# Arduino-Pro-Mini_195x195inch.net
KiCad netlist of a schematic drawn in EAGLE
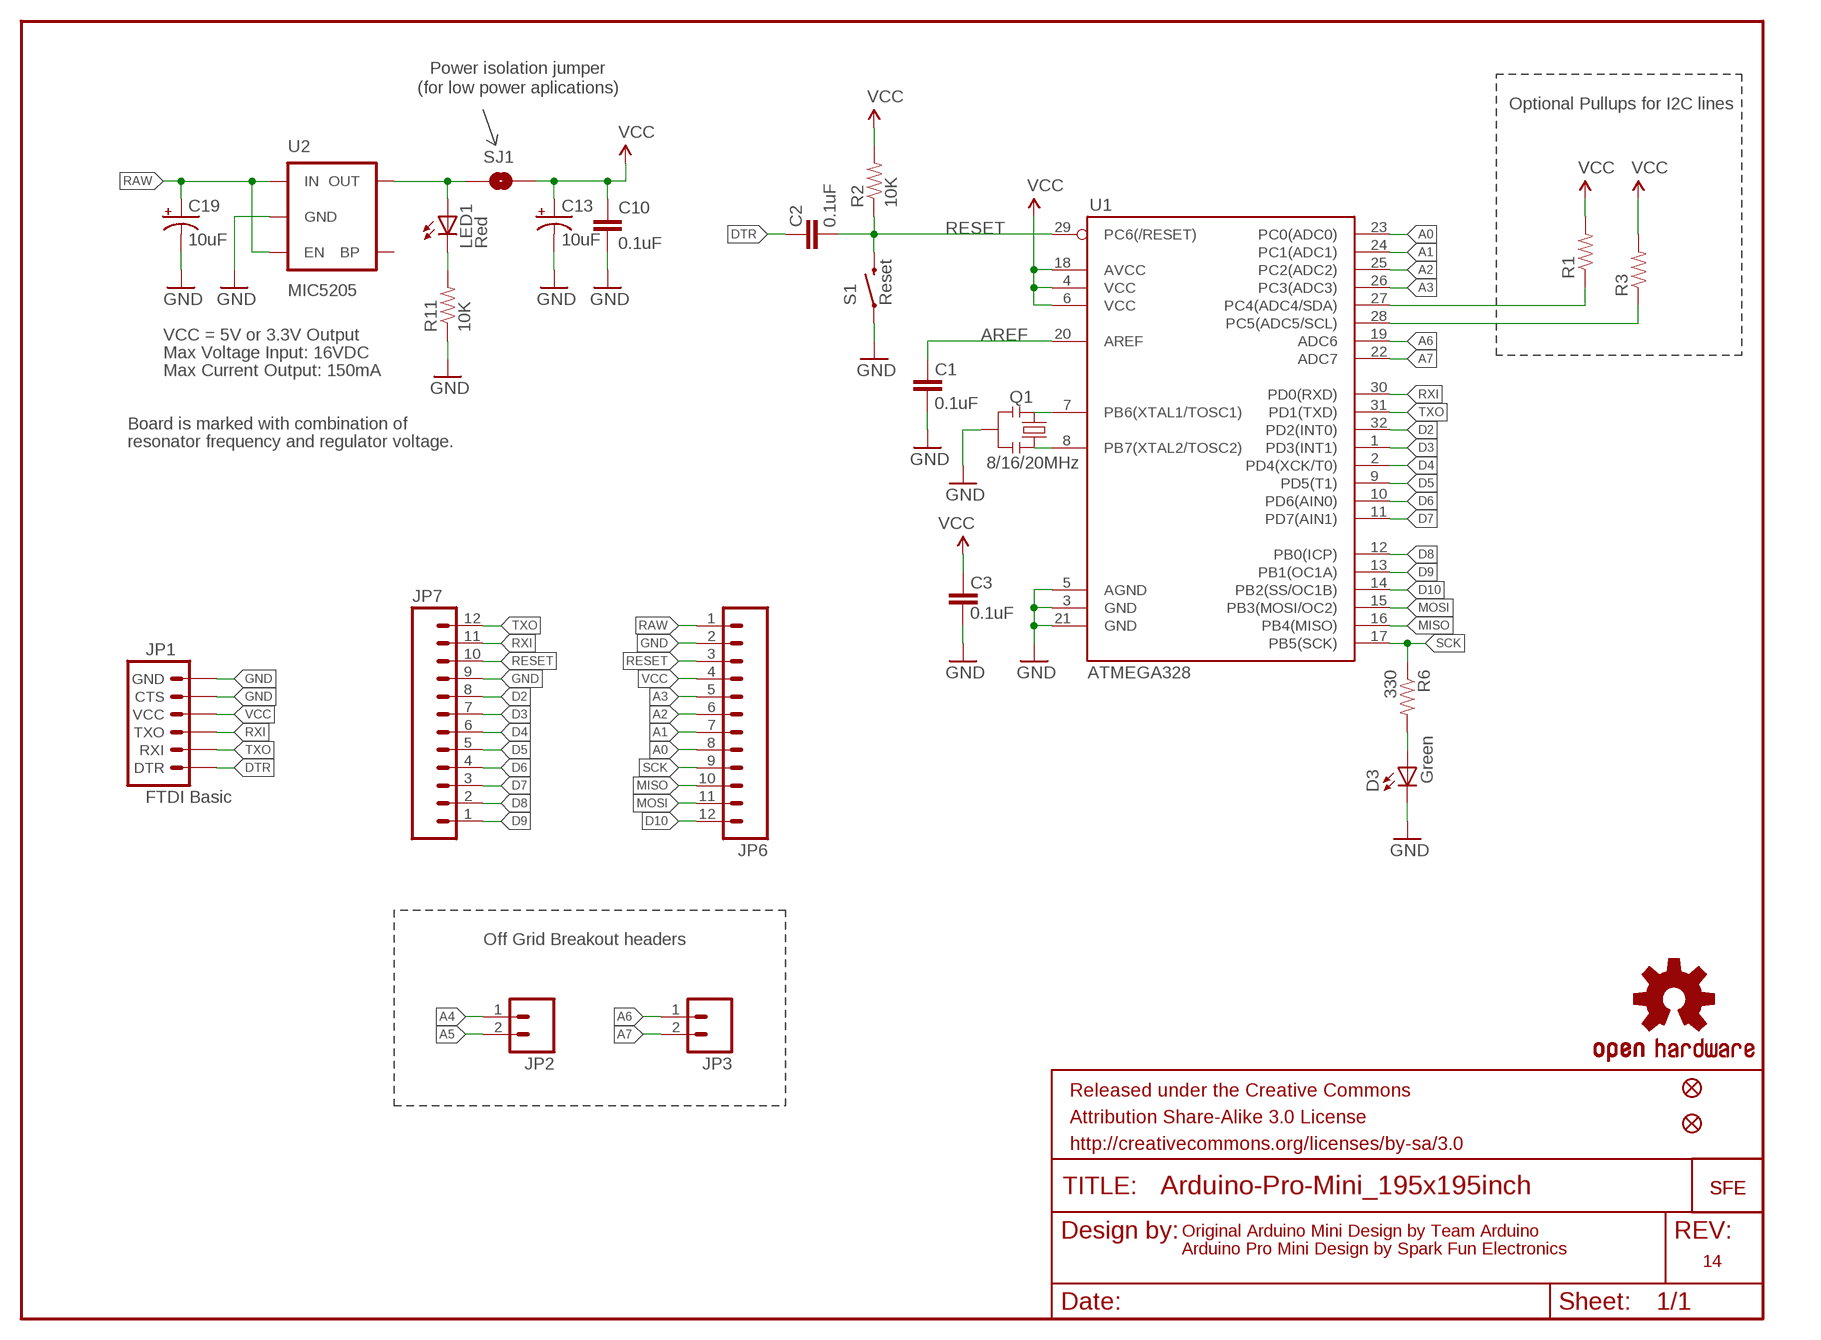
[diagram p0: schematic, sheet 1]

(export (version "E")
  (design (tool "Eeschema 10.0.6"))
  (components
    (comp (ref "C1")
      (value "0.1uF")
      (footprint "eagle-import:0603-CAP")
      (libsource (lib "eagle-import") (part "CAP0603-CAP"))
    )
    (comp (ref "C2")
      (value "0.1uF")
      (footprint "eagle-import:0603-CAP")
      (libsource (lib "eagle-import") (part "CAP0603-CAP"))
    )
    (comp (ref "C3")
      (value "0.1uF")
      (footprint "eagle-import:0603-CAP")
      (libsource (lib "eagle-import") (part "CAP0603-CAP"))
    )
    (comp (ref "C10")
      (value "0.1uF")
      (footprint "eagle-import:0603-CAP")
      (libsource (lib "eagle-import") (part "CAP0603-CAP"))
    )
    (comp (ref "C13")
      (value "10uF")
      (footprint "eagle-import:EIA3216")
      (libsource (lib "eagle-import") (part "CAP_POL1206"))
    )
    (comp (ref "C19")
      (value "10uF")
      (footprint "eagle-import:EIA3216")
      (libsource (lib "eagle-import") (part "CAP_POL1206"))
    )
    (comp (ref "D3")
      (value "Green")
      (footprint "eagle-import:0603-LED-ALT1")
      (libsource (lib "eagle-import") (part "LED"))
    )
    (comp (ref "FRAME1")
      (value "FRAME-LETTER")
      (footprint "eagle-import:CREATIVE_COMMONS")
      (libsource (lib "eagle-import") (part "FRAME-LETTER"))
    )
    (comp (ref "JP1")
      (value "FTDI Basic")
      (footprint "eagle-import:1X06")
      (libsource (lib "eagle-import") (part "ARDUINO_SERIAL_PROGRAMPTH"))
    )
    (comp (ref "JP2")
      (value "M02PTH")
      (footprint "eagle-import:1X02")
      (libsource (lib "eagle-import") (part "M02PTH"))
    )
    (comp (ref "JP3")
      (value "M02PTH")
      (footprint "eagle-import:1X02")
      (libsource (lib "eagle-import") (part "M02PTH"))
    )
    (comp (ref "JP5")
      (value "FIDUCIALUFIDUCIAL")
      (footprint "eagle-import:MICRO-FIDUCIAL")
      (libsource (lib "eagle-import") (part "FIDUCIALUFIDUCIAL"))
    )
    (comp (ref "JP6")
      (value "M12PTH")
      (footprint "eagle-import:1X12")
      (libsource (lib "eagle-import") (part "M12PTH"))
    )
    (comp (ref "JP7")
      (value "M12PTH")
      (footprint "eagle-import:1X12")
      (libsource (lib "eagle-import") (part "M12PTH"))
    )
    (comp (ref "JP8")
      (value "FIDUCIALUFIDUCIAL")
      (footprint "eagle-import:MICRO-FIDUCIAL")
      (libsource (lib "eagle-import") (part "FIDUCIALUFIDUCIAL"))
    )
    (comp (ref "LED1")
      (value "Red")
      (footprint "eagle-import:0603-LED-ALT1")
      (libsource (lib "eagle-import") (part "LED"))
    )
    (comp (ref "Q1")
      (value "8/16/20MHz")
      (footprint "eagle-import:RESONATOR-SMD-1_1")
      (libsource (lib "eagle-import") (part "RESONATOR1{colon}1"))
    )
    (comp (ref "R1")
      (value "RESISTOR0603-RES")
      (footprint "eagle-import:0603-RES")
      (libsource (lib "eagle-import") (part "RESISTOR0603-RES"))
    )
    (comp (ref "R2")
      (value "10K")
      (footprint "eagle-import:0603-RES")
      (libsource (lib "eagle-import") (part "RESISTOR0603-RES"))
    )
    (comp (ref "R3")
      (value "RESISTOR0603-RES")
      (footprint "eagle-import:0603-RES")
      (libsource (lib "eagle-import") (part "RESISTOR0603-RES"))
    )
    (comp (ref "R6")
      (value "330")
      (footprint "eagle-import:0603-RES")
      (libsource (lib "eagle-import") (part "RESISTOR0603-RES"))
    )
    (comp (ref "R11")
      (value "10K")
      (footprint "eagle-import:0603-RES")
      (libsource (lib "eagle-import") (part "RESISTOR0603-RES"))
    )
    (comp (ref "S1")
      (value "Reset")
      (footprint "eagle-import:TACTILE-SWITCH-SMD-ALT01")
      (libsource (lib "eagle-import") (part "SWITCH-MOMENTARY-2SMD-ALT01"))
    )
    (comp (ref "SJ1")
      (value "SOLDERJUMPERNC")
      (footprint "eagle-import:SJ_2S")
      (libsource (lib "eagle-import") (part "SOLDERJUMPERNC"))
    )
    (comp (ref "U$1")
      (value "LOGO-SFESK")
      (footprint "eagle-import:SFE-LOGO-FLAME")
      (libsource (lib "eagle-import") (part "LOGO-SFESK"))
    )
    (comp (ref "U$3")
      (value "OSHW-LOGOS")
      (footprint "eagle-import:OSHW-LOGO-S")
      (libsource (lib "eagle-import") (part "OSHW-LOGOS"))
    )
    (comp (ref "U$11")
      (value "LOGO-SFENEW")
      (footprint "eagle-import:SFE-NEW-WEBLOGO")
      (libsource (lib "eagle-import") (part "LOGO-SFENEW"))
    )
    (comp (ref "U1")
      (value "ATMEGA328")
      (footprint "eagle-import:TQFP32-08")
      (libsource (lib "eagle-import") (part "ATMEGA168"))
    )
    (comp (ref "U2")
      (value "MIC5205")
      (footprint "eagle-import:SOT23-5")
      (libsource (lib "eagle-import") (part "V_REG_LDOSMD"))
    )
  )
  (nets
    (net (code "1") (name "/AREF") (class "Default")
      (node (ref "C1") (pin "2") (pinfunction "2_2") (pintype "passive"))
      (node (ref "U1") (pin "20") (pinfunction "AREF_20") (pintype "bidirectional"))
    )
    (net (code "2") (name "A0") (class "Default")
      (node (ref "JP6") (pin "8") (pinfunction "8_8") (pintype "passive"))
      (node (ref "U1") (pin "23") (pinfunction "PC0(ADC0)_23") (pintype "bidirectional"))
    )
    (net (code "3") (name "A1") (class "Default")
      (node (ref "JP6") (pin "7") (pinfunction "7_7") (pintype "passive"))
      (node (ref "U1") (pin "24") (pinfunction "PC1(ADC1)_24") (pintype "bidirectional"))
    )
    (net (code "4") (name "A2") (class "Default")
      (node (ref "JP6") (pin "6") (pinfunction "6_6") (pintype "passive"))
      (node (ref "U1") (pin "25") (pinfunction "PC2(ADC2)_25") (pintype "bidirectional"))
    )
    (net (code "5") (name "A3") (class "Default")
      (node (ref "JP6") (pin "5") (pinfunction "5_5") (pintype "passive"))
      (node (ref "U1") (pin "26") (pinfunction "PC3(ADC3)_26") (pintype "bidirectional"))
    )
    (net (code "6") (name "A4") (class "Default")
      (node (ref "JP2") (pin "1") (pinfunction "1_1") (pintype "passive"))
      (node (ref "R1") (pin "1") (pinfunction "1_1") (pintype "passive"))
      (node (ref "U1") (pin "27") (pinfunction "PC4(ADC4/SDA)_27") (pintype "bidirectional"))
    )
    (net (code "7") (name "A5") (class "Default")
      (node (ref "JP2") (pin "2") (pinfunction "2_2") (pintype "passive"))
      (node (ref "R3") (pin "1") (pinfunction "1_1") (pintype "passive"))
      (node (ref "U1") (pin "28") (pinfunction "PC5(ADC5/SCL)_28") (pintype "bidirectional"))
    )
    (net (code "8") (name "A6") (class "Default")
      (node (ref "JP3") (pin "1") (pinfunction "1_1") (pintype "passive"))
      (node (ref "U1") (pin "19") (pinfunction "ADC6_19") (pintype "bidirectional"))
    )
    (net (code "9") (name "A7") (class "Default")
      (node (ref "JP3") (pin "2") (pinfunction "2_2") (pintype "passive"))
      (node (ref "U1") (pin "22") (pinfunction "ADC7_22") (pintype "bidirectional"))
    )
    (net (code "10") (name "D2") (class "Default")
      (node (ref "JP7") (pin "8") (pinfunction "8_8") (pintype "passive"))
      (node (ref "U1") (pin "32") (pinfunction "PD2(INT0)_32") (pintype "bidirectional"))
    )
    (net (code "11") (name "D3") (class "Default")
      (node (ref "JP7") (pin "7") (pinfunction "7_7") (pintype "passive"))
      (node (ref "U1") (pin "1") (pinfunction "PD3(INT1)_1") (pintype "bidirectional"))
    )
    (net (code "12") (name "D4") (class "Default")
      (node (ref "JP7") (pin "6") (pinfunction "6_6") (pintype "passive"))
      (node (ref "U1") (pin "2") (pinfunction "PD4(XCK/T0)_2") (pintype "bidirectional"))
    )
    (net (code "13") (name "D5") (class "Default")
      (node (ref "JP7") (pin "5") (pinfunction "5_5") (pintype "passive"))
      (node (ref "U1") (pin "9") (pinfunction "PD5(T1)_9") (pintype "bidirectional"))
    )
    (net (code "14") (name "D6") (class "Default")
      (node (ref "JP7") (pin "4") (pinfunction "4_4") (pintype "passive"))
      (node (ref "U1") (pin "10") (pinfunction "PD6(AIN0)_10") (pintype "bidirectional"))
    )
    (net (code "15") (name "D7") (class "Default")
      (node (ref "JP7") (pin "3") (pinfunction "3_3") (pintype "passive"))
      (node (ref "U1") (pin "11") (pinfunction "PD7(AIN1)_11") (pintype "bidirectional"))
    )
    (net (code "16") (name "D8") (class "Default")
      (node (ref "JP7") (pin "2") (pinfunction "2_2") (pintype "passive"))
      (node (ref "U1") (pin "12") (pinfunction "PB0(ICP)_12") (pintype "bidirectional"))
    )
    (net (code "17") (name "D9") (class "Default")
      (node (ref "JP7") (pin "1") (pinfunction "1_1") (pintype "passive"))
      (node (ref "U1") (pin "13") (pinfunction "PB1(OC1A)_13") (pintype "bidirectional"))
    )
    (net (code "18") (name "D10") (class "Default")
      (node (ref "JP6") (pin "12") (pinfunction "12_12") (pintype "passive"))
      (node (ref "U1") (pin "14") (pinfunction "PB2(SS/OC1B)_14") (pintype "bidirectional"))
    )
    (net (code "19") (name "DTR") (class "Default")
      (node (ref "C2") (pin "2") (pinfunction "2_2") (pintype "passive"))
      (node (ref "JP1") (pin "1") (pinfunction "DTR_1") (pintype "passive"))
    )
    (net (code "20") (name "GND") (class "Default")
      (node (ref "C1") (pin "1") (pinfunction "1_1") (pintype "passive"))
      (node (ref "C10") (pin "2") (pinfunction "2_2") (pintype "passive"))
      (node (ref "C13") (pin "C") (pinfunction "-_C") (pintype "passive"))
      (node (ref "C19") (pin "C") (pinfunction "-_C") (pintype "passive"))
      (node (ref "C3") (pin "1") (pinfunction "1_1") (pintype "passive"))
      (node (ref "D3") (pin "C") (pinfunction "C_C") (pintype "passive"))
      (node (ref "JP1") (pin "5") (pinfunction "CTS_5") (pintype "passive"))
      (node (ref "JP1") (pin "6") (pinfunction "GND_6") (pintype "passive"))
      (node (ref "JP6") (pin "2") (pinfunction "2_2") (pintype "passive"))
      (node (ref "JP7") (pin "9") (pinfunction "9_9") (pintype "passive"))
      (node (ref "Q1") (pin "2") (pinfunction "2_2") (pintype "passive"))
      (node (ref "R11") (pin "1") (pinfunction "1_1") (pintype "passive"))
      (node (ref "S1") (pin "1") (pinfunction "1_1") (pintype "passive"))
      (node (ref "S1") (pin "2") (pinfunction "1_2") (pintype "passive"))
      (node (ref "U1") (pin "21") (pinfunction "GND_21") (pintype "bidirectional"))
      (node (ref "U1") (pin "3") (pinfunction "GND_3") (pintype "bidirectional"))
      (node (ref "U1") (pin "5") (pinfunction "AGND_5") (pintype "bidirectional"))
      (node (ref "U2") (pin "2") (pinfunction "GND_2") (pintype "input"))
    )
    (net (code "21") (name "MISO") (class "Default")
      (node (ref "JP6") (pin "10") (pinfunction "10_10") (pintype "passive"))
      (node (ref "U1") (pin "16") (pinfunction "PB4(MISO)_16") (pintype "bidirectional"))
    )
    (net (code "22") (name "MOSI") (class "Default")
      (node (ref "JP6") (pin "11") (pinfunction "11_11") (pintype "passive"))
      (node (ref "U1") (pin "15") (pinfunction "PB3(MOSI/OC2)_15") (pintype "bidirectional"))
    )
    (net (code "23") (name "Net-(D3-PadA)") (class "Default")
      (node (ref "D3") (pin "A") (pinfunction "A_A") (pintype "passive"))
      (node (ref "R6") (pin "2") (pinfunction "2_2") (pintype "passive"))
    )
    (net (code "24") (name "Net-(LED1-PadC)") (class "Default")
      (node (ref "LED1") (pin "C") (pinfunction "C_C") (pintype "passive"))
      (node (ref "R11") (pin "2") (pinfunction "2_2") (pintype "passive"))
    )
    (net (code "25") (name "Net-(U1-PB6(XTAL1{slash}TOSC1))") (class "Default")
      (node (ref "Q1") (pin "1") (pinfunction "1_1") (pintype "passive"))
      (node (ref "U1") (pin "7") (pinfunction "PB6(XTAL1/TOSC1)_7") (pintype "bidirectional"))
    )
    (net (code "26") (name "Net-(U1-PB7(XTAL2{slash}TOSC2))") (class "Default")
      (node (ref "Q1") (pin "3") (pinfunction "3_3") (pintype "passive"))
      (node (ref "U1") (pin "8") (pinfunction "PB7(XTAL2/TOSC2)_8") (pintype "bidirectional"))
    )
    (net (code "27") (name "Net-(U2-OUT)") (class "Default")
      (node (ref "LED1") (pin "A") (pinfunction "A_A") (pintype "passive"))
      (node (ref "SJ1") (pin "1") (pinfunction "1_1") (pintype "passive"))
      (node (ref "U2") (pin "5") (pinfunction "OUT_5") (pintype "passive"))
    )
    (net (code "28") (name "RAW") (class "Default")
      (node (ref "C19") (pin "A") (pinfunction "+_A") (pintype "passive"))
      (node (ref "JP6") (pin "1") (pinfunction "1_1") (pintype "passive"))
      (node (ref "U2") (pin "1") (pinfunction "IN_1") (pintype "input"))
      (node (ref "U2") (pin "3") (pinfunction "EN_3") (pintype "input"))
    )
    (net (code "29") (name "RESET") (class "Default")
      (node (ref "C2") (pin "1") (pinfunction "1_1") (pintype "passive"))
      (node (ref "JP6") (pin "3") (pinfunction "3_3") (pintype "passive"))
      (node (ref "JP7") (pin "10") (pinfunction "10_10") (pintype "passive"))
      (node (ref "R2") (pin "1") (pinfunction "1_1") (pintype "passive"))
      (node (ref "S1") (pin "3") (pinfunction "2_3") (pintype "passive"))
      (node (ref "S1") (pin "4") (pinfunction "2_4") (pintype "passive"))
      (node (ref "U1") (pin "29") (pinfunction "PC6(/RESET)_29") (pintype "bidirectional"))
    )
    (net (code "30") (name "RXI") (class "Default")
      (node (ref "JP1") (pin "3") (pinfunction "TXO_3") (pintype "passive"))
      (node (ref "JP7") (pin "11") (pinfunction "11_11") (pintype "passive"))
      (node (ref "U1") (pin "30") (pinfunction "PD0(RXD)_30") (pintype "bidirectional"))
    )
    (net (code "31") (name "SCK") (class "Default")
      (node (ref "JP6") (pin "9") (pinfunction "9_9") (pintype "passive"))
      (node (ref "R6") (pin "1") (pinfunction "1_1") (pintype "passive"))
      (node (ref "U1") (pin "17") (pinfunction "PB5(SCK)_17") (pintype "bidirectional"))
    )
    (net (code "32") (name "TXO") (class "Default")
      (node (ref "JP1") (pin "2") (pinfunction "RXI_2") (pintype "passive"))
      (node (ref "JP7") (pin "12") (pinfunction "12_12") (pintype "passive"))
      (node (ref "U1") (pin "31") (pinfunction "PD1(TXD)_31") (pintype "bidirectional"))
    )
    (net (code "33") (name "VCC") (class "Default")
      (node (ref "C10") (pin "1") (pinfunction "1_1") (pintype "passive"))
      (node (ref "C13") (pin "A") (pinfunction "+_A") (pintype "passive"))
      (node (ref "C3") (pin "2") (pinfunction "2_2") (pintype "passive"))
      (node (ref "JP1") (pin "4") (pinfunction "VCC_4") (pintype "passive"))
      (node (ref "JP6") (pin "4") (pinfunction "4_4") (pintype "passive"))
      (node (ref "R1") (pin "2") (pinfunction "2_2") (pintype "passive"))
      (node (ref "R2") (pin "2") (pinfunction "2_2") (pintype "passive"))
      (node (ref "R3") (pin "2") (pinfunction "2_2") (pintype "passive"))
      (node (ref "SJ1") (pin "2") (pinfunction "2_2") (pintype "passive"))
      (node (ref "U1") (pin "18") (pinfunction "AVCC_18") (pintype "bidirectional"))
      (node (ref "U1") (pin "4") (pinfunction "VCC_4") (pintype "bidirectional"))
      (node (ref "U1") (pin "6") (pinfunction "VCC_6") (pintype "bidirectional"))
    )
    (net (code "34") (name "unconnected-(U2-BP-Pad4)") (class "Default")
      (node (ref "U2") (pin "4") (pinfunction "BP_4") (pintype "input"))
    )
  )
)
